# LightStrip.net
KiCad netlist of a schematic drawn in Altium Designer
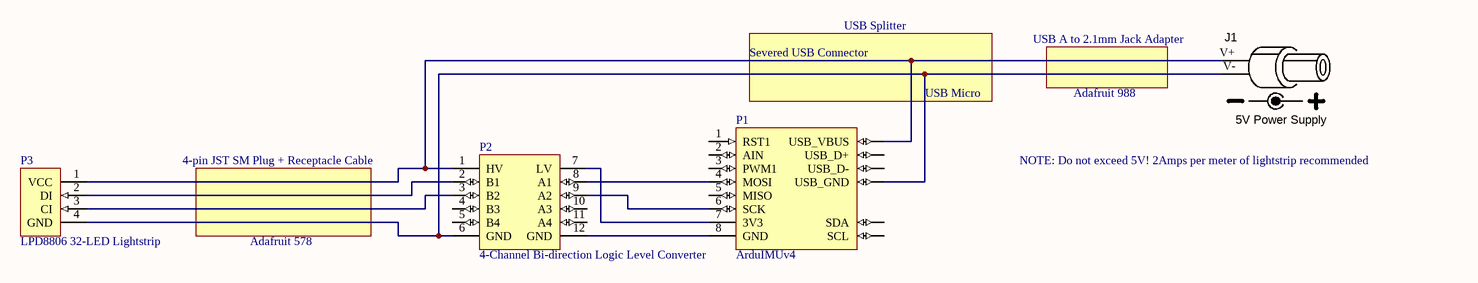
[diagram p0: LightStrip.SchDoc]

(export (version "E")
  (design (tool "Eeschema 10.0.6"))
  (components
    (comp (ref "J1")
      (value "2.1mm ID; 5.5mm OD; Locking Type")
      (footprint "HDR_1x2_Power")
      (description "Power Plug Locking Type 2.1mm ID x 5.5mm OD")
      (fields (field (name "SUPPLIER PART NUMBER 1") "5V Power Supply"))
      (libsource (lib "PBL - Connectors") (part "CONN_PWR_PLUG_2.1x5.5mm"))
    )
    (comp (ref "P1")
      (value "ArduIMUv4")
      (description "ArduIMU v4")
      (libsource (lib "CustomPeripherals") (part "ArduIMUv4"))
    )
    (comp (ref "P2")
      (value "4-Channel Bi-direction Logic Level Converter")
      (libsource (lib "CustomPeripherals") (part "4-Channel Bi-direction Logic Level Converter"))
    )
    (comp (ref "P3")
      (value "LPD8806 32-LED Lightstrip")
      (libsource (lib "CustomPeripherals") (part "LPD8806 32-LED Lightstrip"))
    )
  )
  (nets
    (net (code "1") (name "Net-(P1-3V3)") (class "Default")
      (node (ref "P1") (pin "7") (pinfunction "3V3_7") (pintype "power_in"))
      (node (ref "P2") (pin "7") (pinfunction "LV_7") (pintype "power_in"))
    )
    (net (code "2") (name "Net-(P1-GND)") (class "Default")
      (node (ref "P1") (pin "8") (pinfunction "GND_8") (pintype "power_in"))
      (node (ref "P2") (pin "12") (pinfunction "GND_12") (pintype "power_in"))
    )
    (net (code "3") (name "Net-(P1-MOSI)") (class "Default")
      (node (ref "P1") (pin "4") (pinfunction "MOSI_4") (pintype "bidirectional"))
      (node (ref "P2") (pin "8") (pinfunction "A1_8") (pintype "bidirectional"))
    )
    (net (code "4") (name "Net-(P1-SCK)") (class "Default")
      (node (ref "P1") (pin "6") (pinfunction "SCK_6") (pintype "bidirectional"))
      (node (ref "P2") (pin "9") (pinfunction "A2_9") (pintype "bidirectional"))
    )
    (net (code "5") (name "Net-(P1-USB_GND)") (class "Default")
      (node (ref "J1") (pin "V-") (pinfunction "V-_V-") (pintype "passive"))
      (node (ref "P1") (pin "12") (pinfunction "USB_GND_12") (pintype "bidirectional"))
      (node (ref "P2") (pin "6") (pinfunction "GND_6") (pintype "power_in"))
      (node (ref "P3") (pin "4") (pinfunction "GND_4") (pintype "power_in"))
    )
    (net (code "6") (name "Net-(P1-USB_VBUS)") (class "Default")
      (node (ref "J1") (pin "V+") (pinfunction "V+_V+") (pintype "passive"))
      (node (ref "P1") (pin "9") (pinfunction "USB_VBUS_9") (pintype "bidirectional"))
      (node (ref "P2") (pin "1") (pinfunction "HV_1") (pintype "power_in"))
      (node (ref "P3") (pin "1") (pinfunction "VCC_1") (pintype "power_in"))
    )
    (net (code "7") (name "Net-(P2-B1)") (class "Default")
      (node (ref "P2") (pin "2") (pinfunction "B1_2") (pintype "bidirectional"))
      (node (ref "P3") (pin "2") (pinfunction "DI_2") (pintype "input"))
    )
    (net (code "8") (name "Net-(P2-B2)") (class "Default")
      (node (ref "P2") (pin "3") (pinfunction "B2_3") (pintype "bidirectional"))
      (node (ref "P3") (pin "3") (pinfunction "CI_3") (pintype "input"))
    )
    (net (code "9") (name "unconnected-(P1-AIN-Pad2)") (class "Default")
      (node (ref "P1") (pin "2") (pinfunction "AIN_2") (pintype "bidirectional"))
    )
    (net (code "10") (name "unconnected-(P1-MISO-Pad5)") (class "Default")
      (node (ref "P1") (pin "5") (pinfunction "MISO_5") (pintype "bidirectional"))
    )
    (net (code "11") (name "unconnected-(P1-PWM1-Pad3)") (class "Default")
      (node (ref "P1") (pin "3") (pinfunction "PWM1_3") (pintype "bidirectional"))
    )
    (net (code "12") (name "unconnected-(P1-RST1-Pad1)") (class "Default")
      (node (ref "P1") (pin "1") (pinfunction "RST1_1") (pintype "input"))
    )
    (net (code "13") (name "unconnected-(P1-SCL-Pad14)") (class "Default")
      (node (ref "P1") (pin "14") (pinfunction "SCL_14") (pintype "bidirectional"))
    )
    (net (code "14") (name "unconnected-(P1-SDA-Pad13)") (class "Default")
      (node (ref "P1") (pin "13") (pinfunction "SDA_13") (pintype "bidirectional"))
    )
    (net (code "15") (name "unconnected-(P1-USB_D+-Pad10)") (class "Default")
      (node (ref "P1") (pin "10") (pinfunction "USB_D+_10") (pintype "bidirectional"))
    )
    (net (code "16") (name "unconnected-(P1-USB_D--Pad11)") (class "Default")
      (node (ref "P1") (pin "11") (pinfunction "USB_D-_11") (pintype "bidirectional"))
    )
    (net (code "17") (name "unconnected-(P2-A3-Pad10)") (class "Default")
      (node (ref "P2") (pin "10") (pinfunction "A3_10") (pintype "bidirectional"))
    )
    (net (code "18") (name "unconnected-(P2-A4-Pad11)") (class "Default")
      (node (ref "P2") (pin "11") (pinfunction "A4_11") (pintype "bidirectional"))
    )
    (net (code "19") (name "unconnected-(P2-B3-Pad4)") (class "Default")
      (node (ref "P2") (pin "4") (pinfunction "B3_4") (pintype "bidirectional"))
    )
    (net (code "20") (name "unconnected-(P2-B4-Pad5)") (class "Default")
      (node (ref "P2") (pin "5") (pinfunction "B4_5") (pintype "bidirectional"))
    )
  )
)
